# USB_PCIE.net
KiCad netlist of a schematic drawn in Altium Designer
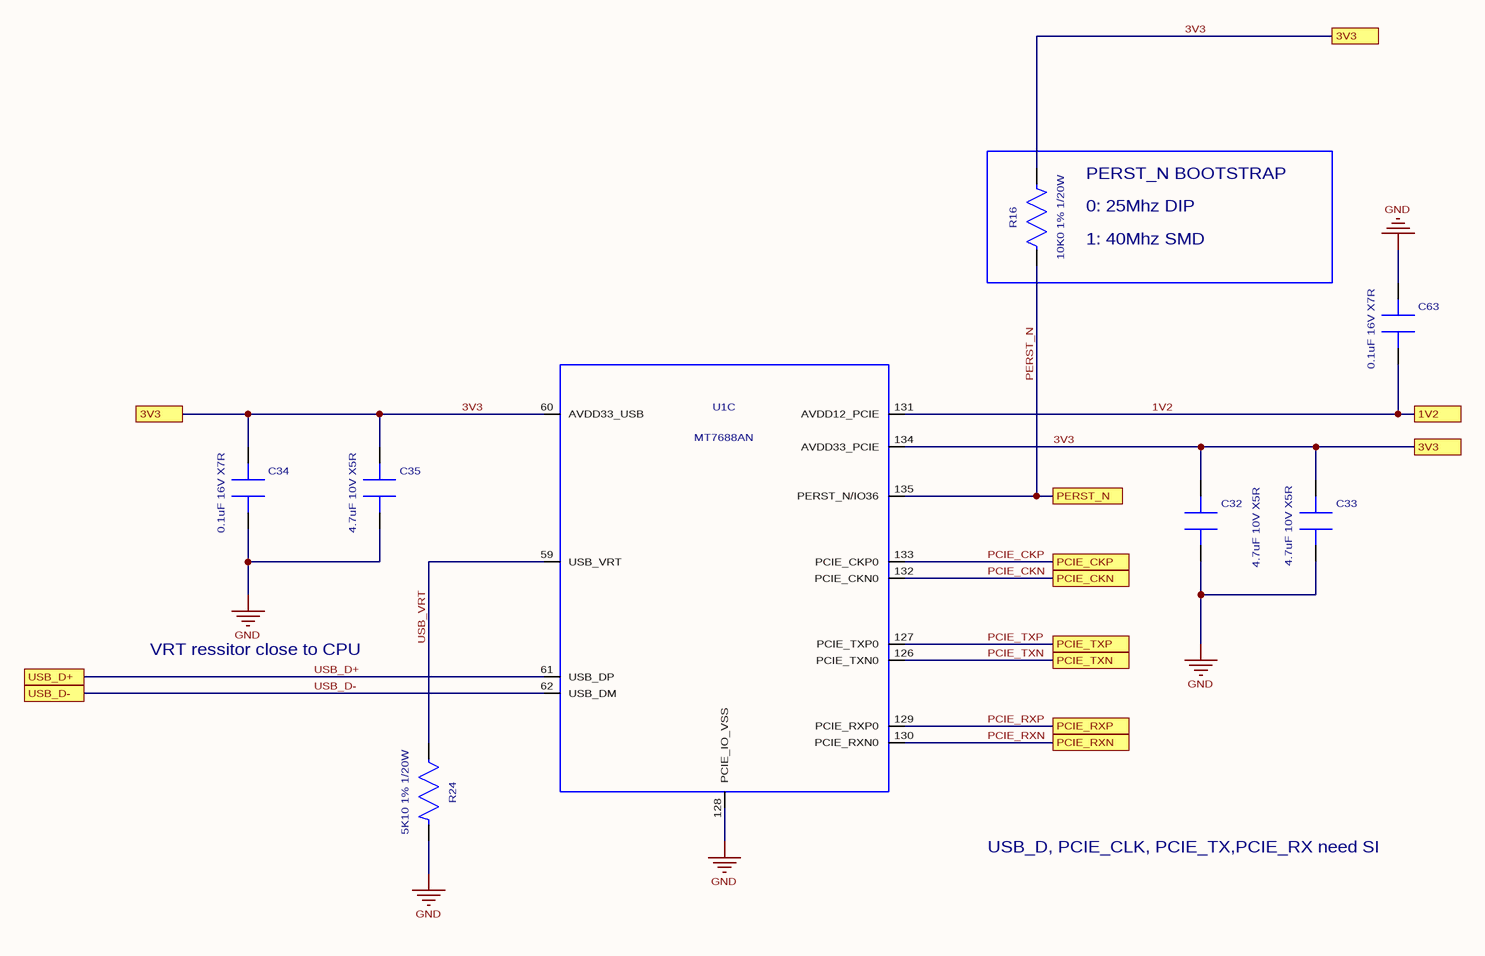
[diagram p0: USB_PCIE.SchDoc]

(export (version "E")
  (design (tool "Eeschema 10.0.6"))
  (components
    (comp (ref "C32")
      (value "4.7uF 10V X5R")
      (footprint "RC0402")
      (description "CAP CER 4.7UF 10V X5R 0402")
      (fields
        (field (name "PART NUMBER") "CL05A475MP5NRNC")
        (field (name "MANUFACTURER") "Samsung Electro-Mechanics")
      )
      (libsource (lib "*") (part "CAP0402-475-10V-X5R"))
    )
    (comp (ref "C33")
      (value "4.7uF 10V X5R")
      (footprint "RC0402")
      (description "CAP CER 4.7UF 10V X5R 0402")
      (fields
        (field (name "PART NUMBER") "CL05A475MP5NRNC")
        (field (name "MANUFACTURER") "Samsung Electro-Mechanics")
      )
      (libsource (lib "*") (part "CAP0402-475-10V-X5R"))
    )
    (comp (ref "C34")
      (value "0.1uF 16V X7R")
      (footprint "RC0201")
      (description "CAP CER 0.1UF 16V X7R 0201")
      (fields
        (field (name "PART NUMBER") "GRM033Z71C104KE14D")
        (field (name "MANUFACTURER") "Murata Electronics")
      )
      (libsource (lib "*") (part "CAP0201-104-16V-X7R"))
    )
    (comp (ref "C35")
      (value "4.7uF 10V X5R")
      (footprint "RC0402")
      (description "CAP CER 4.7UF 10V X5R 0402")
      (fields
        (field (name "PART NUMBER") "CL05A475MP5NRNC")
        (field (name "MANUFACTURER") "Samsung Electro-Mechanics")
      )
      (libsource (lib "*") (part "CAP0402-475-10V-X5R"))
    )
    (comp (ref "C63")
      (value "0.1uF 16V X7R")
      (footprint "RC0201")
      (description "CAP CER 0.1UF 16V X7R 0201")
      (fields
        (field (name "PART NUMBER") "GRM033Z71C104KE14D")
        (field (name "MANUFACTURER") "Murata Electronics")
      )
      (libsource (lib "*") (part "CAP0201-104-16V-X7R"))
    )
    (comp (ref "R16")
      (value "10K0 1% 1/20W")
      (footprint "RC0201")
      (description "RES SMD 10K OHM 1% 1/20W 0201")
      (fields (field (name "MANUFACTURER") "Yageo") (field (name "PART NUMBER") "RC0201FR-0710KP"))
      (libsource (lib "*") (part "RES0201-10K0"))
    )
    (comp (ref "R24")
      (value "5K10 1% 1/20W")
      (footprint "RC0201")
      (description "RES SMD 5.1K OHM 1% 1/20W 0201")
      (fields (field (name "PART NUMBER") "AC0201FR-075K1L") (field (name "MANUFACTURER") "YAGEO"))
      (libsource (lib "*") (part "RES0201-5K10"))
    )
    (comp (ref "U1")
      (value "MT7688AN")
      (footprint "DR-QFN-128")
      (description "580Mhz 32bits Networking Processor")
      (fields (field (name "MANUFACTURER") "MediaTek Inc"))
      (libsource (lib "*") (part "MT7688AN"))
    )
  )
  (nets
    (net (code "1") (name "/1V2") (class "Default")
      (node (ref "C63") (pin "2") (pinfunction "2_2") (pintype "passive"))
      (node (ref "U1") (pin "131") (pinfunction "AVDD12_PCIE_131") (pintype "passive"))
    )
    (net (code "2") (name "/3V3") (class "Default")
      (node (ref "C32") (pin "1") (pinfunction "1_1") (pintype "passive"))
      (node (ref "C33") (pin "1") (pinfunction "1_1") (pintype "passive"))
      (node (ref "C34") (pin "1") (pinfunction "1_1") (pintype "passive"))
      (node (ref "C35") (pin "1") (pinfunction "1_1") (pintype "passive"))
      (node (ref "R16") (pin "2") (pinfunction "2_2") (pintype "passive"))
      (node (ref "U1") (pin "134") (pinfunction "AVDD33_PCIE_134") (pintype "passive"))
      (node (ref "U1") (pin "60") (pinfunction "AVDD33_USB_60") (pintype "passive"))
    )
    (net (code "3") (name "/PCIE_CKN") (class "Default")
      (node (ref "U1") (pin "132") (pinfunction "PCIE_CKN0_132") (pintype "passive"))
    )
    (net (code "4") (name "/PCIE_CKP") (class "Default")
      (node (ref "U1") (pin "133") (pinfunction "PCIE_CKP0_133") (pintype "passive"))
    )
    (net (code "5") (name "/PCIE_RXN") (class "Default")
      (node (ref "U1") (pin "130") (pinfunction "PCIE_RXN0_130") (pintype "passive"))
    )
    (net (code "6") (name "/PCIE_RXP") (class "Default")
      (node (ref "U1") (pin "129") (pinfunction "PCIE_RXP0_129") (pintype "passive"))
    )
    (net (code "7") (name "/PCIE_TXN") (class "Default")
      (node (ref "U1") (pin "126") (pinfunction "PCIE_TXN0_126") (pintype "passive"))
    )
    (net (code "8") (name "/PCIE_TXP") (class "Default")
      (node (ref "U1") (pin "127") (pinfunction "PCIE_TXP0_127") (pintype "passive"))
    )
    (net (code "9") (name "/PERST_N") (class "Default")
      (node (ref "R16") (pin "1") (pinfunction "1_1") (pintype "passive"))
      (node (ref "U1") (pin "135") (pinfunction "PERST_N/IO36_135") (pintype "passive"))
    )
    (net (code "10") (name "/USB_D+") (class "Default")
      (node (ref "U1") (pin "61") (pinfunction "USB_DP_61") (pintype "passive"))
    )
    (net (code "11") (name "/USB_D-") (class "Default")
      (node (ref "U1") (pin "62") (pinfunction "USB_DM_62") (pintype "passive"))
    )
    (net (code "12") (name "/USB_VRT") (class "Default")
      (node (ref "R24") (pin "1") (pinfunction "1_1") (pintype "passive"))
      (node (ref "U1") (pin "59") (pinfunction "USB_VRT_59") (pintype "passive"))
    )
    (net (code "13") (name "GND") (class "Default")
      (node (ref "C32") (pin "2") (pinfunction "2_2") (pintype "passive"))
      (node (ref "C33") (pin "2") (pinfunction "2_2") (pintype "passive"))
      (node (ref "C34") (pin "2") (pinfunction "2_2") (pintype "passive"))
      (node (ref "C35") (pin "2") (pinfunction "2_2") (pintype "passive"))
      (node (ref "C63") (pin "1") (pinfunction "1_1") (pintype "passive"))
      (node (ref "R24") (pin "2") (pinfunction "2_2") (pintype "passive"))
      (node (ref "U1") (pin "128") (pinfunction "PCIE_IO_VSS_128") (pintype "passive"))
    )
  )
)
